# serial.net
KiCad netlist of a schematic drawn in Altium Designer
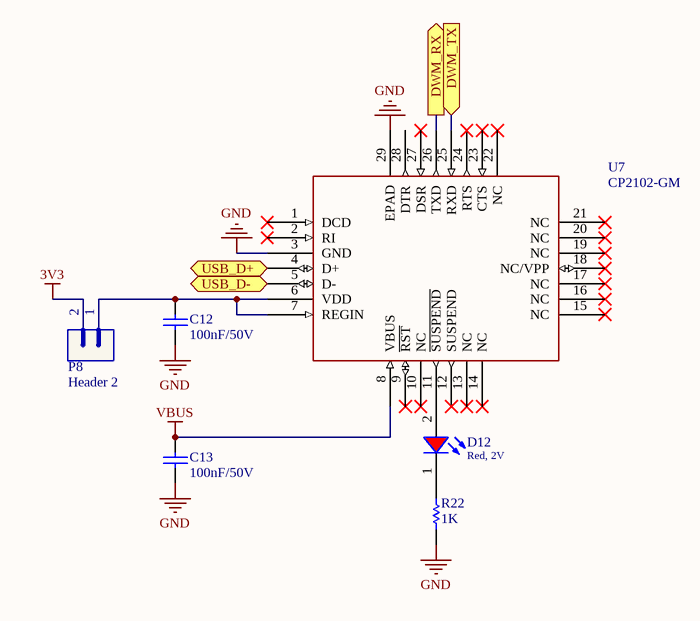
[diagram p0: serial.SchDoc]

(export (version "E")
  (design (tool "Eeschema 10.0.6"))
  (components
    (comp (ref "C12")
      (value "100nF/50V")
      (footprint "CAP-SM-0805")
      (description "CAP CER 0.1UF 50V Y5V 0805")
      (fields
        (field (name "MANUFACTURER") "Samsung Electro-Mechanics")
        (field (name "MANUFACTURER PART NUMBER") "CL21F104ZBCNNNC")
      )
      (libsource (lib "Capacitor") (part "Cap-100nF-50V-0805"))
    )
    (comp (ref "C13")
      (value "100nF/50V")
      (footprint "CAP-SM-0805")
      (description "CAP CER 0.1UF 50V Y5V 0805")
      (fields
        (field (name "MANUFACTURER") "Samsung Electro-Mechanics")
        (field (name "MANUFACTURER PART NUMBER") "CL21F104ZBCNNNC")
      )
      (libsource (lib "Capacitor") (part "Cap-100nF-50V-0805"))
    )
    (comp (ref "D12")
      (value "Red, 2V")
      (footprint "WL-SMCW_0805")
      (description "WL-SMCW SMT Mono-color Chip LED Waterclear, size 0805, Red, 2V, 140deg")
      (fields (field (name "PART NUMBER") "150080RS75000") (field (name "PUBLISHER") "Wurth Elektronik"))
      (libsource (lib "led-smd-0805") (part "150080RS75000"))
    )
    (comp (ref "P8")
      (value "Header 2")
      (footprint "JP2")
      (description "Header, 2-Pin")
      (fields (field (name "LOCAL SUPPLIER PART NUMBER") "x") (field (name "PUBLISHER") "Altium Limited"))
      (libsource (lib "header-connector") (part "Header 2"))
    )
    (comp (ref "R22")
      (value "1K")
      (footprint "resistor-smd:RES-SM-0805")
      (description "RES 1K OHM 1% 1/4W 0805")
      (fields
        (field (name "MANUFACTURER") "Stackpole Electronics Inc")
        (field (name "MANUFACTURER PART NUMBER") "RNCP0805FTD1K00")
      )
      (libsource (lib "resistor-smd") (part "Res-1K-0805"))
    )
    (comp (ref "U7")
      (value "CP2102-GM")
      (footprint "QFN28_5X5_SIL")
      (fields (field (name "COPYRIGHT") "Copyright (C) 2018 Accelerated Designs. All rights reserved"))
      (libsource (lib "functional-ic") (part "CP2102-GM"))
    )
  )
  (nets
    (net (code "1") (name "/DWM_RX") (class "Default")
      (node (ref "U7") (pin "26") (pinfunction "TXD_26") (pintype "output"))
    )
    (net (code "2") (name "/DWM_TX") (class "Default")
      (node (ref "U7") (pin "25") (pinfunction "RXD_25") (pintype "input"))
    )
    (net (code "3") (name "/USB_D+") (class "Default")
      (node (ref "U7") (pin "4") (pinfunction "D+_4") (pintype "bidirectional"))
    )
    (net (code "4") (name "/USB_D-") (class "Default")
      (node (ref "U7") (pin "5") (pinfunction "D-_5") (pintype "bidirectional"))
    )
    (net (code "5") (name "3V3") (class "Default")
      (node (ref "P8") (pin "2") (pinfunction "2_2") (pintype "passive"))
    )
    (net (code "6") (name "GND") (class "Default")
      (node (ref "C12") (pin "1") (pinfunction "1_1") (pintype "passive"))
      (node (ref "C13") (pin "1") (pinfunction "1_1") (pintype "passive"))
      (node (ref "R22") (pin "1") (pinfunction "1_1") (pintype "passive"))
      (node (ref "U7") (pin "29") (pinfunction "EPAD_29") (pintype "passive"))
      (node (ref "U7") (pin "3") (pinfunction "GND_3") (pintype "power_in"))
    )
    (net (code "7") (name "Net-(D12-A)") (class "Default")
      (node (ref "D12") (pin "2") (pinfunction "A_2") (pintype "passive"))
      (node (ref "U7") (pin "11") (pinfunction "~{SUSPEND}_11") (pintype "output"))
    )
    (net (code "8") (name "Net-(D12-K)") (class "Default")
      (node (ref "D12") (pin "1") (pinfunction "K_1") (pintype "passive"))
      (node (ref "R22") (pin "2") (pinfunction "2_2") (pintype "passive"))
    )
    (net (code "9") (name "Net-(U7-REGIN)") (class "Default")
      (node (ref "C12") (pin "2") (pinfunction "2_2") (pintype "passive"))
      (node (ref "P8") (pin "1") (pinfunction "1_1") (pintype "passive"))
      (node (ref "U7") (pin "6") (pinfunction "VDD_6") (pintype "power_in"))
      (node (ref "U7") (pin "7") (pinfunction "REGIN_7") (pintype "input"))
    )
    (net (code "10") (name "VBUS") (class "Default")
      (node (ref "C13") (pin "2") (pinfunction "2_2") (pintype "passive"))
      (node (ref "U7") (pin "8") (pinfunction "VBUS_8") (pintype "input"))
    )
    (net (code "11") (name "unconnected-(U7-CTS-Pad23)") (class "Default")
      (node (ref "U7") (pin "23") (pinfunction "CTS_23") (pintype "input+no_connect"))
    )
    (net (code "12") (name "unconnected-(U7-DCD-Pad1)") (class "Default")
      (node (ref "U7") (pin "1") (pinfunction "DCD_1") (pintype "input+no_connect"))
    )
    (net (code "13") (name "unconnected-(U7-DSR-Pad27)") (class "Default")
      (node (ref "U7") (pin "27") (pinfunction "DSR_27") (pintype "input+no_connect"))
    )
    (net (code "14") (name "unconnected-(U7-DTR-Pad28)") (class "Default")
      (node (ref "U7") (pin "28") (pinfunction "DTR_28") (pintype "output"))
    )
    (net (code "15") (name "unconnected-(U7-NC-Pad10)") (class "Default")
      (node (ref "U7") (pin "10") (pinfunction "NC_10") (pintype "passive+no_connect"))
    )
    (net (code "16") (name "unconnected-(U7-NC-Pad13)") (class "Default")
      (node (ref "U7") (pin "13") (pinfunction "NC_13") (pintype "passive+no_connect"))
    )
    (net (code "17") (name "unconnected-(U7-NC-Pad14)") (class "Default")
      (node (ref "U7") (pin "14") (pinfunction "NC_14") (pintype "passive+no_connect"))
    )
    (net (code "18") (name "unconnected-(U7-NC-Pad15)") (class "Default")
      (node (ref "U7") (pin "15") (pinfunction "NC_15") (pintype "passive+no_connect"))
    )
    (net (code "19") (name "unconnected-(U7-NC-Pad16)") (class "Default")
      (node (ref "U7") (pin "16") (pinfunction "NC_16") (pintype "passive+no_connect"))
    )
    (net (code "20") (name "unconnected-(U7-NC-Pad17)") (class "Default")
      (node (ref "U7") (pin "17") (pinfunction "NC_17") (pintype "passive+no_connect"))
    )
    (net (code "21") (name "unconnected-(U7-NC-Pad19)") (class "Default")
      (node (ref "U7") (pin "19") (pinfunction "NC_19") (pintype "passive+no_connect"))
    )
    (net (code "22") (name "unconnected-(U7-NC-Pad20)") (class "Default")
      (node (ref "U7") (pin "20") (pinfunction "NC_20") (pintype "passive+no_connect"))
    )
    (net (code "23") (name "unconnected-(U7-NC-Pad21)") (class "Default")
      (node (ref "U7") (pin "21") (pinfunction "NC_21") (pintype "passive+no_connect"))
    )
    (net (code "24") (name "unconnected-(U7-NC-Pad22)") (class "Default")
      (node (ref "U7") (pin "22") (pinfunction "NC_22") (pintype "passive+no_connect"))
    )
    (net (code "25") (name "unconnected-(U7-NC{slash}VPP-Pad18)") (class "Default")
      (node (ref "U7") (pin "18") (pinfunction "NC/VPP_18") (pintype "bidirectional+no_connect"))
    )
    (net (code "26") (name "unconnected-(U7-RI-Pad2)") (class "Default")
      (node (ref "U7") (pin "2") (pinfunction "RI_2") (pintype "input+no_connect"))
    )
    (net (code "27") (name "unconnected-(U7-RTS-Pad24)") (class "Default")
      (node (ref "U7") (pin "24") (pinfunction "RTS_24") (pintype "output+no_connect"))
    )
    (net (code "28") (name "unconnected-(U7-SUSPEND-Pad12)") (class "Default")
      (node (ref "U7") (pin "12") (pinfunction "SUSPEND_12") (pintype "output+no_connect"))
    )
    (net (code "29") (name "unconnected-(U7-~{RST}-Pad9)") (class "Default")
      (node (ref "U7") (pin "9") (pinfunction "~{RST}_9") (pintype "bidirectional+no_connect"))
    )
  )
)
